# down.net
KiCad netlist of a schematic drawn in EAGLE
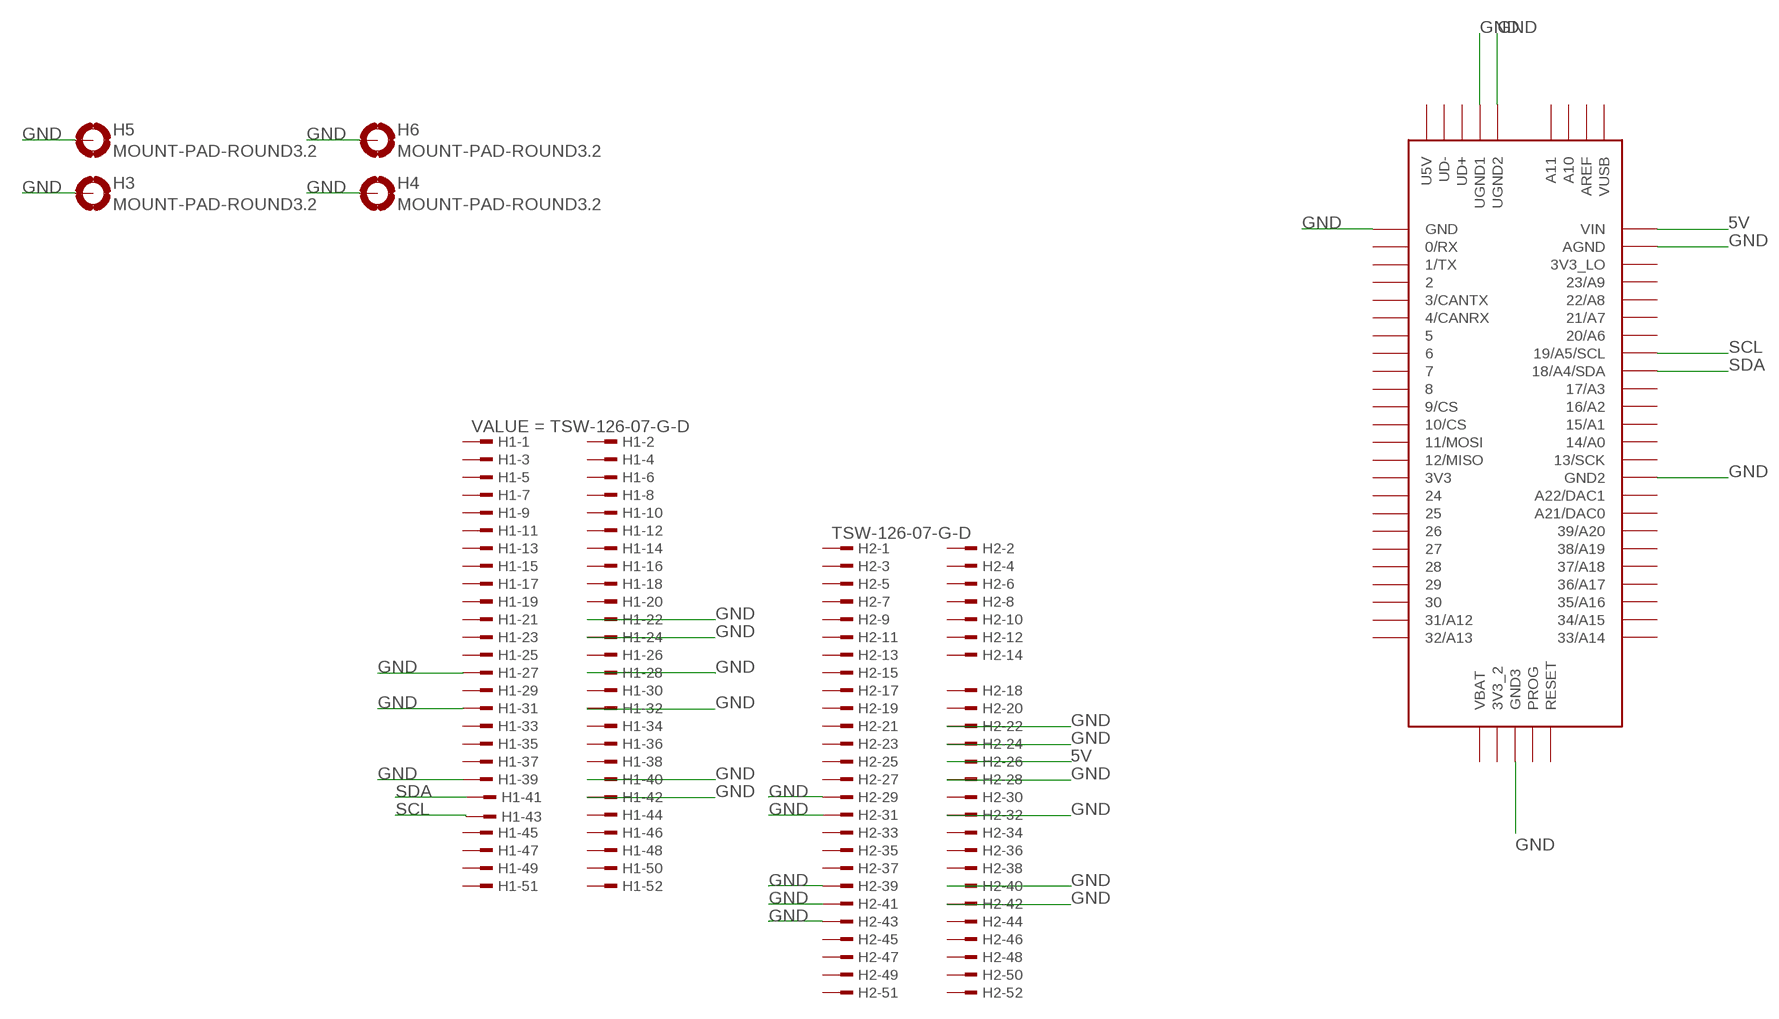
[diagram p0: schematic, sheet 2, part 1 of 2]
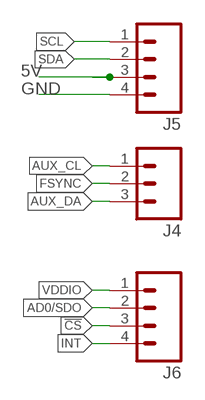
[diagram p1: schematic, sheet 2, part 2 of 2]

(export (version "E")
  (design (tool "Eeschema 10.0.6"))
  (components
    (comp (ref "H1")
      (value "TSW-126-07-G-D")
      (footprint "eagle-import:TSW-126-XX-G-D")
      (fields (field (name "MF") "Samtec Inc."))
      (libsource (lib "eagle-import") (part "TSW-126--G-D07"))
    )
    (comp (ref "H2")
      (value "TSW-126-07-G-D")
      (footprint "eagle-import:TSW-126-XX-G-D")
      (fields (field (name "MF") "Samtec Inc."))
      (libsource (lib "eagle-import") (part "TSW-126--G-D07"))
    )
    (comp (ref "H3")
      (value "MOUNT-PAD-ROUND3.2")
      (footprint "eagle-import:3,2-PAD")
      (libsource (lib "eagle-import") (part "MOUNT-PAD-ROUND3.2"))
    )
    (comp (ref "H4")
      (value "MOUNT-PAD-ROUND3.2")
      (footprint "eagle-import:3,2-PAD")
      (libsource (lib "eagle-import") (part "MOUNT-PAD-ROUND3.2"))
    )
    (comp (ref "H5")
      (value "MOUNT-PAD-ROUND3.2")
      (footprint "eagle-import:3,2-PAD")
      (libsource (lib "eagle-import") (part "MOUNT-PAD-ROUND3.2"))
    )
    (comp (ref "H6")
      (value "MOUNT-PAD-ROUND3.2")
      (footprint "eagle-import:3,2-PAD")
      (libsource (lib "eagle-import") (part "MOUNT-PAD-ROUND3.2"))
    )
    (comp (ref "J4")
      (value "M03PTH")
      (footprint "eagle-import:1X03")
      (libsource (lib "eagle-import") (part "M03PTH"))
    )
    (comp (ref "J5")
      (value "M04PTH")
      (footprint "eagle-import:1X04")
      (libsource (lib "eagle-import") (part "M04PTH"))
    )
    (comp (ref "J6")
      (value "M04PTH")
      (footprint "eagle-import:1X04")
      (libsource (lib "eagle-import") (part "M04PTH"))
    )
    (comp (ref "U$1")
      (value "TEENSY_3.5/3.6")
      (footprint "eagle-import:TEENSY_3.5_3.6")
      (libsource (lib "eagle-import") (part "TEENSY_3.5/3.6"))
    )
  )
  (nets
    (net (code "1") (name "5V") (class "Default")
      (node (ref "H2") (pin "26") (pinfunction "1_26") (pintype "passive"))
      (node (ref "J5") (pin "3") (pinfunction "3_3") (pintype "passive"))
      (node (ref "U$1") (pin "VIN") (pinfunction "VIN_VIN") (pintype "bidirectional"))
    )
    (net (code "2") (name "AD0{slash}SDO") (class "Default")
      (node (ref "J6") (pin "2") (pinfunction "2_2") (pintype "passive"))
    )
    (net (code "3") (name "AUX_CL") (class "Default")
      (node (ref "J4") (pin "1") (pinfunction "1_1") (pintype "passive"))
    )
    (net (code "4") (name "AUX_DA") (class "Default")
      (node (ref "J4") (pin "3") (pinfunction "3_3") (pintype "passive"))
    )
    (net (code "5") (name "FSYNC") (class "Default")
      (node (ref "J4") (pin "2") (pinfunction "2_2") (pintype "passive"))
    )
    (net (code "6") (name "GND") (class "Default")
      (node (ref "H1") (pin "22") (pinfunction "1_22") (pintype "passive"))
      (node (ref "H1") (pin "24") (pinfunction "1_24") (pintype "passive"))
      (node (ref "H1") (pin "27") (pinfunction "1_27") (pintype "passive"))
      (node (ref "H1") (pin "28") (pinfunction "1_28") (pintype "passive"))
      (node (ref "H1") (pin "31") (pinfunction "1_31") (pintype "passive"))
      (node (ref "H1") (pin "32") (pinfunction "1_32") (pintype "passive"))
      (node (ref "H1") (pin "39") (pinfunction "1_39") (pintype "passive"))
      (node (ref "H1") (pin "40") (pinfunction "1_40") (pintype "passive"))
      (node (ref "H1") (pin "42") (pinfunction "1_42") (pintype "passive"))
      (node (ref "H2") (pin "22") (pinfunction "1_22") (pintype "passive"))
      (node (ref "H2") (pin "24") (pinfunction "1_24") (pintype "passive"))
      (node (ref "H2") (pin "28") (pinfunction "1_28") (pintype "passive"))
      (node (ref "H2") (pin "29") (pinfunction "1_29") (pintype "passive"))
      (node (ref "H2") (pin "31") (pinfunction "1_31") (pintype "passive"))
      (node (ref "H2") (pin "32") (pinfunction "1_32") (pintype "passive"))
      (node (ref "H2") (pin "39") (pinfunction "1_39") (pintype "passive"))
      (node (ref "H2") (pin "40") (pinfunction "1_40") (pintype "passive"))
      (node (ref "H2") (pin "41") (pinfunction "1_41") (pintype "passive"))
      (node (ref "H2") (pin "42") (pinfunction "1_42") (pintype "passive"))
      (node (ref "H2") (pin "43") (pinfunction "1_43") (pintype "passive"))
      (node (ref "H3") (pin "B3,2") (pinfunction "MOUNT_B3,2") (pintype "passive"))
      (node (ref "H4") (pin "B3,2") (pinfunction "MOUNT_B3,2") (pintype "passive"))
      (node (ref "H5") (pin "B3,2") (pinfunction "MOUNT_B3,2") (pintype "passive"))
      (node (ref "H6") (pin "B3,2") (pinfunction "MOUNT_B3,2") (pintype "passive"))
      (node (ref "J5") (pin "4") (pinfunction "4_4") (pintype "passive"))
      (node (ref "U$1") (pin "AGND") (pinfunction "AGND_AGND") (pintype "bidirectional"))
      (node (ref "U$1") (pin "GND") (pinfunction "GND_GND") (pintype "bidirectional"))
      (node (ref "U$1") (pin "GND2") (pinfunction "GND2_GND2") (pintype "bidirectional"))
      (node (ref "U$1") (pin "GND3") (pinfunction "GND3_GND3") (pintype "bidirectional"))
      (node (ref "U$1") (pin "UGND1") (pinfunction "UGND1_UGND1") (pintype "bidirectional"))
      (node (ref "U$1") (pin "UGND2") (pinfunction "UGND2_UGND2") (pintype "bidirectional"))
    )
    (net (code "7") (name "INT") (class "Default")
      (node (ref "J6") (pin "4") (pinfunction "4_4") (pintype "passive"))
    )
    (net (code "8") (name "SCL") (class "Default")
      (node (ref "H1") (pin "43") (pinfunction "1_43") (pintype "passive"))
      (node (ref "J5") (pin "1") (pinfunction "1_1") (pintype "passive"))
      (node (ref "U$1") (pin "19/A5/SCL") (pinfunction "19/A5/SCL_19/A5/SCL") (pintype "bidirectional"))
    )
    (net (code "9") (name "SDA") (class "Default")
      (node (ref "H1") (pin "41") (pinfunction "1_41") (pintype "passive"))
      (node (ref "J5") (pin "2") (pinfunction "2_2") (pintype "passive"))
      (node (ref "U$1") (pin "18/A4/SDA") (pinfunction "18/A4/SDA_18/A4/SDA") (pintype "bidirectional"))
    )
    (net (code "10") (name "VDDIO") (class "Default")
      (node (ref "J6") (pin "1") (pinfunction "1_1") (pintype "passive"))
    )
    (net (code "11") (name "unconnected-(H1-Pad1)") (class "Default")
      (node (ref "H1") (pin "1") (pinfunction "1_1") (pintype "passive"))
    )
    (net (code "12") (name "unconnected-(H1AA-1-Pad33)") (class "Default")
      (node (ref "H1") (pin "33") (pinfunction "1_33") (pintype "passive"))
    )
    (net (code "13") (name "unconnected-(H1AB-1-Pad34)") (class "Default")
      (node (ref "H1") (pin "34") (pinfunction "1_34") (pintype "passive"))
    )
    (net (code "14") (name "unconnected-(H1AC-1-Pad35)") (class "Default")
      (node (ref "H1") (pin "35") (pinfunction "1_35") (pintype "passive"))
    )
    (net (code "15") (name "unconnected-(H1AD-1-Pad36)") (class "Default")
      (node (ref "H1") (pin "36") (pinfunction "1_36") (pintype "passive"))
    )
    (net (code "16") (name "unconnected-(H1AE-1-Pad37)") (class "Default")
      (node (ref "H1") (pin "37") (pinfunction "1_37") (pintype "passive"))
    )
    (net (code "17") (name "unconnected-(H1AF-1-Pad38)") (class "Default")
      (node (ref "H1") (pin "38") (pinfunction "1_38") (pintype "passive"))
    )
    (net (code "18") (name "unconnected-(H1AH-1-Pad4)") (class "Default")
      (node (ref "H1") (pin "4") (pinfunction "1_4") (pintype "passive"))
    )
    (net (code "19") (name "unconnected-(H1AM-1-Pad44)") (class "Default")
      (node (ref "H1") (pin "44") (pinfunction "1_44") (pintype "passive"))
    )
    (net (code "20") (name "unconnected-(H1AN-1-Pad45)") (class "Default")
      (node (ref "H1") (pin "45") (pinfunction "1_45") (pintype "passive"))
    )
    (net (code "21") (name "unconnected-(H1AO-1-Pad46)") (class "Default")
      (node (ref "H1") (pin "46") (pinfunction "1_46") (pintype "passive"))
    )
    (net (code "22") (name "unconnected-(H1AP-1-Pad47)") (class "Default")
      (node (ref "H1") (pin "47") (pinfunction "1_47") (pintype "passive"))
    )
    (net (code "23") (name "unconnected-(H1AQ-1-Pad48)") (class "Default")
      (node (ref "H1") (pin "48") (pinfunction "1_48") (pintype "passive"))
    )
    (net (code "24") (name "unconnected-(H1AR-1-Pad49)") (class "Default")
      (node (ref "H1") (pin "49") (pinfunction "1_49") (pintype "passive"))
    )
    (net (code "25") (name "unconnected-(H1AS-1-Pad5)") (class "Default")
      (node (ref "H1") (pin "5") (pinfunction "1_5") (pintype "passive"))
    )
    (net (code "26") (name "unconnected-(H1AT-1-Pad50)") (class "Default")
      (node (ref "H1") (pin "50") (pinfunction "1_50") (pintype "passive"))
    )
    (net (code "27") (name "unconnected-(H1AU-1-Pad51)") (class "Default")
      (node (ref "H1") (pin "51") (pinfunction "1_51") (pintype "passive"))
    )
    (net (code "28") (name "unconnected-(H1AV-1-Pad52)") (class "Default")
      (node (ref "H1") (pin "52") (pinfunction "1_52") (pintype "passive"))
    )
    (net (code "29") (name "unconnected-(H1AW-1-Pad6)") (class "Default")
      (node (ref "H1") (pin "6") (pinfunction "1_6") (pintype "passive"))
    )
    (net (code "30") (name "unconnected-(H1AX-1-Pad7)") (class "Default")
      (node (ref "H1") (pin "7") (pinfunction "1_7") (pintype "passive"))
    )
    (net (code "31") (name "unconnected-(H1AY-1-Pad8)") (class "Default")
      (node (ref "H1") (pin "8") (pinfunction "1_8") (pintype "passive"))
    )
    (net (code "32") (name "unconnected-(H1AZ-1-Pad9)") (class "Default")
      (node (ref "H1") (pin "9") (pinfunction "1_9") (pintype "passive"))
    )
    (net (code "33") (name "unconnected-(H1B-1-Pad10)") (class "Default")
      (node (ref "H1") (pin "10") (pinfunction "1_10") (pintype "passive"))
    )
    (net (code "34") (name "unconnected-(H1C-1-Pad11)") (class "Default")
      (node (ref "H1") (pin "11") (pinfunction "1_11") (pintype "passive"))
    )
    (net (code "35") (name "unconnected-(H1D-1-Pad12)") (class "Default")
      (node (ref "H1") (pin "12") (pinfunction "1_12") (pintype "passive"))
    )
    (net (code "36") (name "unconnected-(H1E-1-Pad13)") (class "Default")
      (node (ref "H1") (pin "13") (pinfunction "1_13") (pintype "passive"))
    )
    (net (code "37") (name "unconnected-(H1F-1-Pad14)") (class "Default")
      (node (ref "H1") (pin "14") (pinfunction "1_14") (pintype "passive"))
    )
    (net (code "38") (name "unconnected-(H1G-1-Pad15)") (class "Default")
      (node (ref "H1") (pin "15") (pinfunction "1_15") (pintype "passive"))
    )
    (net (code "39") (name "unconnected-(H1H-1-Pad16)") (class "Default")
      (node (ref "H1") (pin "16") (pinfunction "1_16") (pintype "passive"))
    )
    (net (code "40") (name "unconnected-(H1I-1-Pad17)") (class "Default")
      (node (ref "H1") (pin "17") (pinfunction "1_17") (pintype "passive"))
    )
    (net (code "41") (name "unconnected-(H1J-1-Pad18)") (class "Default")
      (node (ref "H1") (pin "18") (pinfunction "1_18") (pintype "passive"))
    )
    (net (code "42") (name "unconnected-(H1K-1-Pad19)") (class "Default")
      (node (ref "H1") (pin "19") (pinfunction "1_19") (pintype "passive"))
    )
    (net (code "43") (name "unconnected-(H1L-1-Pad2)") (class "Default")
      (node (ref "H1") (pin "2") (pinfunction "1_2") (pintype "passive"))
    )
    (net (code "44") (name "unconnected-(H1M-1-Pad20)") (class "Default")
      (node (ref "H1") (pin "20") (pinfunction "1_20") (pintype "passive"))
    )
    (net (code "45") (name "unconnected-(H1N-1-Pad21)") (class "Default")
      (node (ref "H1") (pin "21") (pinfunction "1_21") (pintype "passive"))
    )
    (net (code "46") (name "unconnected-(H1P-1-Pad23)") (class "Default")
      (node (ref "H1") (pin "23") (pinfunction "1_23") (pintype "passive"))
    )
    (net (code "47") (name "unconnected-(H1R-1-Pad25)") (class "Default")
      (node (ref "H1") (pin "25") (pinfunction "1_25") (pintype "passive"))
    )
    (net (code "48") (name "unconnected-(H1S-1-Pad26)") (class "Default")
      (node (ref "H1") (pin "26") (pinfunction "1_26") (pintype "passive"))
    )
    (net (code "49") (name "unconnected-(H1V-1-Pad29)") (class "Default")
      (node (ref "H1") (pin "29") (pinfunction "1_29") (pintype "passive"))
    )
    (net (code "50") (name "unconnected-(H1W-1-Pad3)") (class "Default")
      (node (ref "H1") (pin "3") (pinfunction "1_3") (pintype "passive"))
    )
    (net (code "51") (name "unconnected-(H1X-1-Pad30)") (class "Default")
      (node (ref "H1") (pin "30") (pinfunction "1_30") (pintype "passive"))
    )
    (net (code "52") (name "unconnected-(H2-Pad1)") (class "Default")
      (node (ref "H2") (pin "1") (pinfunction "1_1") (pintype "passive"))
    )
    (net (code "53") (name "unconnected-(H2AA-1-Pad33)") (class "Default")
      (node (ref "H2") (pin "33") (pinfunction "1_33") (pintype "passive"))
    )
    (net (code "54") (name "unconnected-(H2AB-1-Pad34)") (class "Default")
      (node (ref "H2") (pin "34") (pinfunction "1_34") (pintype "passive"))
    )
    (net (code "55") (name "unconnected-(H2AC-1-Pad35)") (class "Default")
      (node (ref "H2") (pin "35") (pinfunction "1_35") (pintype "passive"))
    )
    (net (code "56") (name "unconnected-(H2AD-1-Pad36)") (class "Default")
      (node (ref "H2") (pin "36") (pinfunction "1_36") (pintype "passive"))
    )
    (net (code "57") (name "unconnected-(H2AE-1-Pad37)") (class "Default")
      (node (ref "H2") (pin "37") (pinfunction "1_37") (pintype "passive"))
    )
    (net (code "58") (name "unconnected-(H2AF-1-Pad38)") (class "Default")
      (node (ref "H2") (pin "38") (pinfunction "1_38") (pintype "passive"))
    )
    (net (code "59") (name "unconnected-(H2AH-1-Pad4)") (class "Default")
      (node (ref "H2") (pin "4") (pinfunction "1_4") (pintype "passive"))
    )
    (net (code "60") (name "unconnected-(H2AM-1-Pad44)") (class "Default")
      (node (ref "H2") (pin "44") (pinfunction "1_44") (pintype "passive"))
    )
    (net (code "61") (name "unconnected-(H2AN-1-Pad45)") (class "Default")
      (node (ref "H2") (pin "45") (pinfunction "1_45") (pintype "passive"))
    )
    (net (code "62") (name "unconnected-(H2AO-1-Pad46)") (class "Default")
      (node (ref "H2") (pin "46") (pinfunction "1_46") (pintype "passive"))
    )
    (net (code "63") (name "unconnected-(H2AP-1-Pad47)") (class "Default")
      (node (ref "H2") (pin "47") (pinfunction "1_47") (pintype "passive"))
    )
    (net (code "64") (name "unconnected-(H2AQ-1-Pad48)") (class "Default")
      (node (ref "H2") (pin "48") (pinfunction "1_48") (pintype "passive"))
    )
    (net (code "65") (name "unconnected-(H2AR-1-Pad49)") (class "Default")
      (node (ref "H2") (pin "49") (pinfunction "1_49") (pintype "passive"))
    )
    (net (code "66") (name "unconnected-(H2AS-1-Pad5)") (class "Default")
      (node (ref "H2") (pin "5") (pinfunction "1_5") (pintype "passive"))
    )
    (net (code "67") (name "unconnected-(H2AT-1-Pad50)") (class "Default")
      (node (ref "H2") (pin "50") (pinfunction "1_50") (pintype "passive"))
    )
    (net (code "68") (name "unconnected-(H2AU-1-Pad51)") (class "Default")
      (node (ref "H2") (pin "51") (pinfunction "1_51") (pintype "passive"))
    )
    (net (code "69") (name "unconnected-(H2AV-1-Pad52)") (class "Default")
      (node (ref "H2") (pin "52") (pinfunction "1_52") (pintype "passive"))
    )
    (net (code "70") (name "unconnected-(H2AW-1-Pad6)") (class "Default")
      (node (ref "H2") (pin "6") (pinfunction "1_6") (pintype "passive"))
    )
    (net (code "71") (name "unconnected-(H2AX-1-Pad7)") (class "Default")
      (node (ref "H2") (pin "7") (pinfunction "1_7") (pintype "passive"))
    )
    (net (code "72") (name "unconnected-(H2AY-1-Pad8)") (class "Default")
      (node (ref "H2") (pin "8") (pinfunction "1_8") (pintype "passive"))
    )
    (net (code "73") (name "unconnected-(H2AZ-1-Pad9)") (class "Default")
      (node (ref "H2") (pin "9") (pinfunction "1_9") (pintype "passive"))
    )
    (net (code "74") (name "unconnected-(H2B-1-Pad10)") (class "Default")
      (node (ref "H2") (pin "10") (pinfunction "1_10") (pintype "passive"))
    )
    (net (code "75") (name "unconnected-(H2C-1-Pad11)") (class "Default")
      (node (ref "H2") (pin "11") (pinfunction "1_11") (pintype "passive"))
    )
    (net (code "76") (name "unconnected-(H2D-1-Pad12)") (class "Default")
      (node (ref "H2") (pin "12") (pinfunction "1_12") (pintype "passive"))
    )
    (net (code "77") (name "unconnected-(H2E-1-Pad13)") (class "Default")
      (node (ref "H2") (pin "13") (pinfunction "1_13") (pintype "passive"))
    )
    (net (code "78") (name "unconnected-(H2F-1-Pad14)") (class "Default")
      (node (ref "H2") (pin "14") (pinfunction "1_14") (pintype "passive"))
    )
    (net (code "79") (name "unconnected-(H2G-1-Pad15)") (class "Default")
      (node (ref "H2") (pin "15") (pinfunction "1_15") (pintype "passive"))
    )
    (net (code "80") (name "unconnected-(H2I-1-Pad17)") (class "Default")
      (node (ref "H2") (pin "17") (pinfunction "1_17") (pintype "passive"))
    )
    (net (code "81") (name "unconnected-(H2J-1-Pad18)") (class "Default")
      (node (ref "H2") (pin "18") (pinfunction "1_18") (pintype "passive"))
    )
    (net (code "82") (name "unconnected-(H2K-1-Pad19)") (class "Default")
      (node (ref "H2") (pin "19") (pinfunction "1_19") (pintype "passive"))
    )
    (net (code "83") (name "unconnected-(H2L-1-Pad2)") (class "Default")
      (node (ref "H2") (pin "2") (pinfunction "1_2") (pintype "passive"))
    )
    (net (code "84") (name "unconnected-(H2M-1-Pad20)") (class "Default")
      (node (ref "H2") (pin "20") (pinfunction "1_20") (pintype "passive"))
    )
    (net (code "85") (name "unconnected-(H2N-1-Pad21)") (class "Default")
      (node (ref "H2") (pin "21") (pinfunction "1_21") (pintype "passive"))
    )
    (net (code "86") (name "unconnected-(H2P-1-Pad23)") (class "Default")
      (node (ref "H2") (pin "23") (pinfunction "1_23") (pintype "passive"))
    )
    (net (code "87") (name "unconnected-(H2R-1-Pad25)") (class "Default")
      (node (ref "H2") (pin "25") (pinfunction "1_25") (pintype "passive"))
    )
    (net (code "88") (name "unconnected-(H2T-1-Pad27)") (class "Default")
      (node (ref "H2") (pin "27") (pinfunction "1_27") (pintype "passive"))
    )
    (net (code "89") (name "unconnected-(H2W-1-Pad3)") (class "Default")
      (node (ref "H2") (pin "3") (pinfunction "1_3") (pintype "passive"))
    )
    (net (code "90") (name "unconnected-(H2X-1-Pad30)") (class "Default")
      (node (ref "H2") (pin "30") (pinfunction "1_30") (pintype "passive"))
    )
    (net (code "91") (name "unconnected-(U$1-A21{slash}DAC0-Pad21{slash}DAC0)") (class "Default")
      (node (ref "U$1") (pin "21/DAC0") (pinfunction "A21/DAC0_21/DAC0") (pintype "bidirectional"))
    )
    (net (code "92") (name "unconnected-(U$1-Pad0{slash}RX)") (class "Default")
      (node (ref "U$1") (pin "0/RX") (pinfunction "0/RX_0/RX") (pintype "bidirectional"))
    )
    (net (code "93") (name "unconnected-(U$1-Pad1{slash}TX)") (class "Default")
      (node (ref "U$1") (pin "1/TX") (pinfunction "1/TX_1/TX") (pintype "bidirectional"))
    )
    (net (code "94") (name "unconnected-(U$1-Pad2)") (class "Default")
      (node (ref "U$1") (pin "2") (pinfunction "2_2") (pintype "bidirectional"))
    )
    (net (code "95") (name "unconnected-(U$1-Pad3V3)") (class "Default")
      (node (ref "U$1") (pin "3V3") (pinfunction "3V3_3V3") (pintype "bidirectional"))
    )
    (net (code "96") (name "unconnected-(U$1-Pad3V3_2)") (class "Default")
      (node (ref "U$1") (pin "3V3_2") (pinfunction "3V3_2_3V3_2") (pintype "bidirectional"))
    )
    (net (code "97") (name "unconnected-(U$1-Pad3V3_LO)") (class "Default")
      (node (ref "U$1") (pin "3V3_LO") (pinfunction "3V3_LO_3V3_LO") (pintype "bidirectional"))
    )
    (net (code "98") (name "unconnected-(U$1-Pad3{slash}CANTX)") (class "Default")
      (node (ref "U$1") (pin "3/CANTX") (pinfunction "3/CANTX_3/CANTX") (pintype "bidirectional"))
    )
    (net (code "99") (name "unconnected-(U$1-Pad4{slash}CANRX)") (class "Default")
      (node (ref "U$1") (pin "4/CANRX") (pinfunction "4/CANRX_4/CANRX") (pintype "bidirectional"))
    )
    (net (code "100") (name "unconnected-(U$1-Pad5)") (class "Default")
      (node (ref "U$1") (pin "5") (pinfunction "5_5") (pintype "bidirectional"))
    )
    (net (code "101") (name "unconnected-(U$1-Pad6)") (class "Default")
      (node (ref "U$1") (pin "6") (pinfunction "6_6") (pintype "bidirectional"))
    )
    (net (code "102") (name "unconnected-(U$1-Pad7)") (class "Default")
      (node (ref "U$1") (pin "7") (pinfunction "7_7") (pintype "bidirectional"))
    )
    (net (code "103") (name "unconnected-(U$1-Pad8)") (class "Default")
      (node (ref "U$1") (pin "8") (pinfunction "8_8") (pintype "bidirectional"))
    )
    (net (code "104") (name "unconnected-(U$1-Pad9{slash}CS)") (class "Default")
      (node (ref "U$1") (pin "9/CS") (pinfunction "9/CS_9/CS") (pintype "bidirectional"))
    )
    (net (code "105") (name "unconnected-(U$1-Pad10{slash}CS)") (class "Default")
      (node (ref "U$1") (pin "10/CS") (pinfunction "10/CS_10/CS") (pintype "bidirectional"))
    )
    (net (code "106") (name "unconnected-(U$1-Pad11{slash}MOSI)") (class "Default")
      (node (ref "U$1") (pin "11/MOSI") (pinfunction "11/MOSI_11/MOSI") (pintype "bidirectional"))
    )
    (net (code "107") (name "unconnected-(U$1-Pad12{slash}MISO)") (class "Default")
      (node (ref "U$1") (pin "12/MISO") (pinfunction "12/MISO_12/MISO") (pintype "bidirectional"))
    )
    (net (code "108") (name "unconnected-(U$1-Pad13{slash}SCK)") (class "Default")
      (node (ref "U$1") (pin "13/SCK") (pinfunction "13/SCK_13/SCK") (pintype "bidirectional"))
    )
    (net (code "109") (name "unconnected-(U$1-Pad14{slash}A0)") (class "Default")
      (node (ref "U$1") (pin "14/A0") (pinfunction "14/A0_14/A0") (pintype "bidirectional"))
    )
    (net (code "110") (name "unconnected-(U$1-Pad15{slash}A1)") (class "Default")
      (node (ref "U$1") (pin "15/A1") (pinfunction "15/A1_15/A1") (pintype "bidirectional"))
    )
    (net (code "111") (name "unconnected-(U$1-Pad16{slash}A2)") (class "Default")
      (node (ref "U$1") (pin "16/A2") (pinfunction "16/A2_16/A2") (pintype "bidirectional"))
    )
    (net (code "112") (name "unconnected-(U$1-Pad17{slash}A3)") (class "Default")
      (node (ref "U$1") (pin "17/A3") (pinfunction "17/A3_17/A3") (pintype "bidirectional"))
    )
    (net (code "113") (name "unconnected-(U$1-Pad20{slash}A6)") (class "Default")
      (node (ref "U$1") (pin "20/A6") (pinfunction "20/A6_20/A6") (pintype "bidirectional"))
    )
    (net (code "114") (name "unconnected-(U$1-Pad21{slash}A7)") (class "Default")
      (node (ref "U$1") (pin "21/A7") (pinfunction "21/A7_21/A7") (pintype "bidirectional"))
    )
    (net (code "115") (name "unconnected-(U$1-Pad22{slash}A8)") (class "Default")
      (node (ref "U$1") (pin "22/A8") (pinfunction "22/A8_22/A8") (pintype "bidirectional"))
    )
    (net (code "116") (name "unconnected-(U$1-Pad23{slash}A9)") (class "Default")
      (node (ref "U$1") (pin "23/A9") (pinfunction "23/A9_23/A9") (pintype "bidirectional"))
    )
    (net (code "117") (name "unconnected-(U$1-Pad24)") (class "Default")
      (node (ref "U$1") (pin "24") (pinfunction "24_24") (pintype "bidirectional"))
    )
    (net (code "118") (name "unconnected-(U$1-Pad25)") (class "Default")
      (node (ref "U$1") (pin "25") (pinfunction "25_25") (pintype "bidirectional"))
    )
    (net (code "119") (name "unconnected-(U$1-Pad26)") (class "Default")
      (node (ref "U$1") (pin "26") (pinfunction "26_26") (pintype "bidirectional"))
    )
    (net (code "120") (name "unconnected-(U$1-Pad27)") (class "Default")
      (node (ref "U$1") (pin "27") (pinfunction "27_27") (pintype "bidirectional"))
    )
    (net (code "121") (name "unconnected-(U$1-Pad28)") (class "Default")
      (node (ref "U$1") (pin "28") (pinfunction "28_28") (pintype "bidirectional"))
    )
    (net (code "122") (name "unconnected-(U$1-Pad29)") (class "Default")
      (node (ref "U$1") (pin "29") (pinfunction "29_29") (pintype "bidirectional"))
    )
    (net (code "123") (name "unconnected-(U$1-Pad30)") (class "Default")
      (node (ref "U$1") (pin "30") (pinfunction "30_30") (pintype "bidirectional"))
    )
    (net (code "124") (name "unconnected-(U$1-Pad31{slash}A12)") (class "Default")
      (node (ref "U$1") (pin "31/A12") (pinfunction "31/A12_31/A12") (pintype "bidirectional"))
    )
    (net (code "125") (name "unconnected-(U$1-Pad32{slash}A13)") (class "Default")
      (node (ref "U$1") (pin "32/A13") (pinfunction "32/A13_32/A13") (pintype "bidirectional"))
    )
    (net (code "126") (name "unconnected-(U$1-Pad33{slash}A14)") (class "Default")
      (node (ref "U$1") (pin "33/A14") (pinfunction "33/A14_33/A14") (pintype "bidirectional"))
    )
    (net (code "127") (name "unconnected-(U$1-Pad34{slash}A15)") (class "Default")
      (node (ref "U$1") (pin "34/A15") (pinfunction "34/A15_34/A15") (pintype "bidirectional"))
    )
    (net (code "128") (name "unconnected-(U$1-Pad35{slash}A16)") (class "Default")
      (node (ref "U$1") (pin "35/A16") (pinfunction "35/A16_35/A16") (pintype "bidirectional"))
    )
    (net (code "129") (name "unconnected-(U$1-Pad36{slash}A17)") (class "Default")
      (node (ref "U$1") (pin "36/A17") (pinfunction "36/A17_36/A17") (pintype "bidirectional"))
    )
    (net (code "130") (name "unconnected-(U$1-Pad37{slash}A18)") (class "Default")
      (node (ref "U$1") (pin "37/A18") (pinfunction "37/A18_37/A18") (pintype "bidirectional"))
    )
    (net (code "131") (name "unconnected-(U$1-Pad38{slash}A19)") (class "Default")
      (node (ref "U$1") (pin "38/A19") (pinfunction "38/A19_38/A19") (pintype "bidirectional"))
    )
    (net (code "132") (name "unconnected-(U$1-Pad39{slash}A20)") (class "Default")
      (node (ref "U$1") (pin "39/A20") (pinfunction "39/A20_39/A20") (pintype "bidirectional"))
    )
    (net (code "133") (name "unconnected-(U$1-PadA10)") (class "Default")
      (node (ref "U$1") (pin "A10") (pinfunction "A10_A10") (pintype "bidirectional"))
    )
    (net (code "134") (name "unconnected-(U$1-PadA11)") (class "Default")
      (node (ref "U$1") (pin "A11") (pinfunction "A11_A11") (pintype "bidirectional"))
    )
    (net (code "135") (name "unconnected-(U$1-PadA22{slash}DAC1)") (class "Default")
      (node (ref "U$1") (pin "A22/DAC1") (pinfunction "A22/DAC1_A22/DAC1") (pintype "bidirectional"))
    )
    (net (code "136") (name "unconnected-(U$1-PadAREF)") (class "Default")
      (node (ref "U$1") (pin "AREF") (pinfunction "AREF_AREF") (pintype "bidirectional"))
    )
    (net (code "137") (name "unconnected-(U$1-PadPROG)") (class "Default")
      (node (ref "U$1") (pin "PROG") (pinfunction "PROG_PROG") (pintype "bidirectional"))
    )
    (net (code "138") (name "unconnected-(U$1-PadRESET)") (class "Default")
      (node (ref "U$1") (pin "RESET") (pinfunction "RESET_RESET") (pintype "bidirectional"))
    )
    (net (code "139") (name "unconnected-(U$1-PadU5V)") (class "Default")
      (node (ref "U$1") (pin "U5V") (pinfunction "U5V_U5V") (pintype "bidirectional"))
    )
    (net (code "140") (name "unconnected-(U$1-PadUD+)") (class "Default")
      (node (ref "U$1") (pin "UD+") (pinfunction "UD+_UD+") (pintype "bidirectional"))
    )
    (net (code "141") (name "unconnected-(U$1-PadUD-)") (class "Default")
      (node (ref "U$1") (pin "UD-") (pinfunction "UD-_UD-") (pintype "bidirectional"))
    )
    (net (code "142") (name "unconnected-(U$1-PadVBAT)") (class "Default")
      (node (ref "U$1") (pin "VBAT") (pinfunction "VBAT_VBAT") (pintype "bidirectional"))
    )
    (net (code "143") (name "unconnected-(U$1-PadVUSB)") (class "Default")
      (node (ref "U$1") (pin "VUSB") (pinfunction "VUSB_VUSB") (pintype "bidirectional"))
    )
    (net (code "144") (name "~{CS}") (class "Default")
      (node (ref "J6") (pin "3") (pinfunction "3_3") (pintype "passive"))
    )
  )
)
